# LAB2.net
KiCad netlist of a schematic drawn in Altium Designer
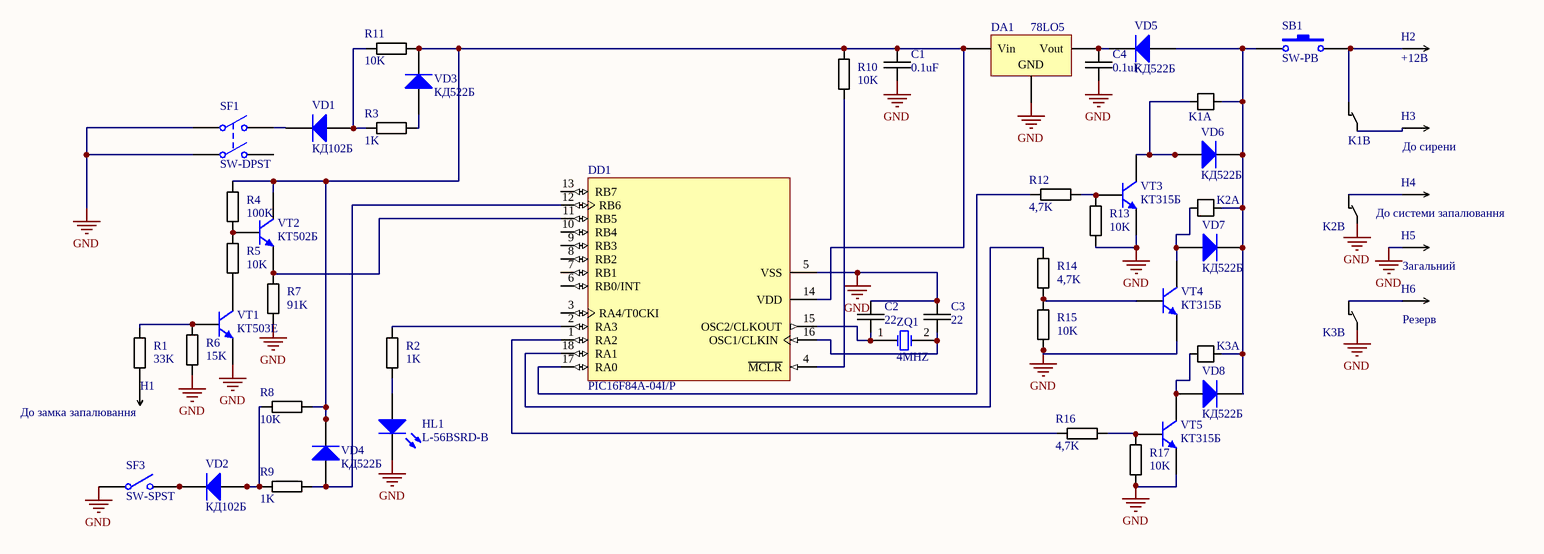
[diagram p0: LAB2.SchDoc]

(export (version "E")
  (design (tool "Eeschema 10.0.6"))
  (components
    (comp (ref "C1")
      (value "0.1uF")
      (footprint "CAPACITOR 1206")
      (libsource (lib "Maks_lib") (part "Capasitor"))
    )
    (comp (ref "C2")
      (value "22")
      (footprint "CAPACITOR 1206")
      (libsource (lib "Maks_lib") (part "Capasitor"))
    )
    (comp (ref "C3")
      (value "22")
      (footprint "CAPACITOR 1206")
      (libsource (lib "Maks_lib") (part "Capasitor"))
    )
    (comp (ref "C4")
      (value "0.1uF")
      (footprint "CAPACITOR 1206")
      (libsource (lib "Maks_lib") (part "Capasitor"))
    )
    (comp (ref "DA1")
      (value "78LO5")
      (footprint "D2PAK_N")
      (description "Voltage Regulator")
      (fields (field (name "PUBLISHER") "Altium Limited"))
      (libsource (lib "Miscellaneous Devices") (part "Volt Reg"))
    )
    (comp (ref "DD1")
      (value "PIC16F84A-04I/P")
      (footprint "PDIP300-P18")
      (libsource (lib "Altium Content Vault") (part "MC-8B-16F84A-IL18"))
    )
    (comp (ref "H1")
      (value "До замка запалювання")
      (footprint "Hole 2.5")
      (libsource (lib "Maks_lib") (part "Hole"))
    )
    (comp (ref "H2") (value "+12В") (footprint "Hole 2.5") (libsource (lib "Maks_lib") (part "Hole")))
    (comp (ref "H3") (value "До сирени") (footprint "Hole 2.5") (libsource (lib "Maks_lib") (part "Hole")))
    (comp (ref "H4")
      (value "До системи запалювання")
      (footprint "Hole 2.5")
      (libsource (lib "Maks_lib") (part "Hole"))
    )
    (comp (ref "H5") (value "Загальний") (footprint "Hole 2.5") (libsource (lib "Maks_lib") (part "Hole")))
    (comp (ref "H6") (value "Резерв") (footprint "Hole 2.5") (libsource (lib "Maks_lib") (part "Hole")))
    (comp (ref "HL1")
      (value "L-56BSRD-B")
      (footprint "LED-1")
      (description "Typical RED GaAs LED")
      (fields (field (name "PUBLISHER") "Altium Limited"))
      (libsource (lib "Miscellaneous Devices") (part "LED1"))
    )
    (comp (ref "K1")
      (value "Relay SPST")
      (footprint "g2rl-1a-e")
      (libsource (lib "Maks_lib") (part "Relay SPST"))
    )
    (comp (ref "K2")
      (value "Relay SPST")
      (footprint "g2rl-1a-e")
      (libsource (lib "Maks_lib") (part "Relay SPST"))
    )
    (comp (ref "K3")
      (value "Relay SPST")
      (footprint "g2rl-1a-e")
      (libsource (lib "Maks_lib") (part "Relay SPST"))
    )
    (comp (ref "R1") (value "33K") (footprint "Resistor 1206") (libsource (lib "Maks_lib") (part "Resistor")))
    (comp (ref "R2") (value "1K") (footprint "Resistor 1206") (libsource (lib "Maks_lib") (part "Resistor")))
    (comp (ref "R3") (value "1K") (footprint "Resistor 1206") (libsource (lib "Maks_lib") (part "Resistor")))
    (comp (ref "R4")
      (value "100K")
      (footprint "Resistor 1206")
      (libsource (lib "Maks_lib") (part "Resistor"))
    )
    (comp (ref "R5") (value "10K") (footprint "Resistor 1206") (libsource (lib "Maks_lib") (part "Resistor")))
    (comp (ref "R6") (value "15K") (footprint "Resistor 1206") (libsource (lib "Maks_lib") (part "Resistor")))
    (comp (ref "R7") (value "91K") (footprint "Resistor 1206") (libsource (lib "Maks_lib") (part "Resistor")))
    (comp (ref "R8") (value "10K") (footprint "Resistor 1206") (libsource (lib "Maks_lib") (part "Resistor")))
    (comp (ref "R9") (value "1K") (footprint "Resistor 1206") (libsource (lib "Maks_lib") (part "Resistor")))
    (comp (ref "R10")
      (value "10K")
      (footprint "Resistor 1206")
      (libsource (lib "Maks_lib") (part "Resistor"))
    )
    (comp (ref "R11")
      (value "10K")
      (footprint "Resistor 1206")
      (libsource (lib "Maks_lib") (part "Resistor"))
    )
    (comp (ref "R12")
      (value "4,7K")
      (footprint "Resistor 1206")
      (libsource (lib "Maks_lib") (part "Resistor"))
    )
    (comp (ref "R13")
      (value "10K")
      (footprint "Resistor 1206")
      (libsource (lib "Maks_lib") (part "Resistor"))
    )
    (comp (ref "R14")
      (value "4,7K")
      (footprint "Resistor 1206")
      (libsource (lib "Maks_lib") (part "Resistor"))
    )
    (comp (ref "R15")
      (value "10K")
      (footprint "Resistor 1206")
      (libsource (lib "Maks_lib") (part "Resistor"))
    )
    (comp (ref "R16")
      (value "4,7K")
      (footprint "Resistor 1206")
      (libsource (lib "Maks_lib") (part "Resistor"))
    )
    (comp (ref "R17")
      (value "10K")
      (footprint "Resistor 1206")
      (libsource (lib "Maks_lib") (part "Resistor"))
    )
    (comp (ref "SB1")
      (value "SW-PB")
      (footprint "SPST-2")
      (description "Switch")
      (fields (field (name "PUBLISHER") "Altium Limited"))
      (libsource (lib "Miscellaneous Devices") (part "SW-PB"))
    )
    (comp (ref "SF1")
      (value "SW-DPST")
      (footprint "DPST-4")
      (description "Double-Pole, Single-Throw Switch")
      (fields (field (name "PUBLISHER") "Altium Limited"))
      (libsource (lib "Miscellaneous Devices") (part "SW-DPST"))
    )
    (comp (ref "SF3")
      (value "SW-SPST")
      (footprint "SPST-2")
      (description "Single-Pole, Single-Throw Switch")
      (fields (field (name "PUBLISHER") "Altium Limited"))
      (libsource (lib "Miscellaneous Devices") (part "SW-SPST"))
    )
    (comp (ref "VD1")
      (value "КД102Б")
      (footprint "DO-35")
      (description "High Conductance Fast Diode")
      (fields (field (name "PUBLISHER") "Altium Limited"))
      (libsource (lib "Miscellaneous Devices") (part "Diode 1N4448"))
    )
    (comp (ref "VD2")
      (value "КД102Б")
      (footprint "DO-35")
      (description "High Conductance Fast Diode")
      (fields (field (name "PUBLISHER") "Altium Limited"))
      (libsource (lib "Miscellaneous Devices") (part "Diode 1N4448"))
    )
    (comp (ref "VD3")
      (value "КД522Б")
      (footprint "DO-35")
      (description "High Conductance Fast Diode")
      (fields (field (name "PUBLISHER") "Altium Limited"))
      (libsource (lib "Miscellaneous Devices") (part "Diode 1N4448"))
    )
    (comp (ref "VD4")
      (value "КД522Б")
      (footprint "DO-35")
      (description "High Conductance Fast Diode")
      (fields (field (name "PUBLISHER") "Altium Limited"))
      (libsource (lib "Miscellaneous Devices") (part "Diode 1N4448"))
    )
    (comp (ref "VD5")
      (value "КД522Б")
      (footprint "DO-35")
      (description "High Conductance Fast Diode")
      (fields (field (name "PUBLISHER") "Altium Limited"))
      (libsource (lib "Miscellaneous Devices") (part "Diode 1N4448"))
    )
    (comp (ref "VD6")
      (value "КД522Б")
      (footprint "DO-35")
      (description "High Conductance Fast Diode")
      (fields (field (name "PUBLISHER") "Altium Limited"))
      (libsource (lib "Miscellaneous Devices") (part "Diode 1N4448"))
    )
    (comp (ref "VD7")
      (value "КД522Б")
      (footprint "DO-35")
      (description "High Conductance Fast Diode")
      (fields (field (name "PUBLISHER") "Altium Limited"))
      (libsource (lib "Miscellaneous Devices") (part "Diode 1N4448"))
    )
    (comp (ref "VD8")
      (value "КД522Б")
      (footprint "DO-35")
      (description "High Conductance Fast Diode")
      (fields (field (name "PUBLISHER") "Altium Limited"))
      (libsource (lib "Miscellaneous Devices") (part "Diode 1N4448"))
    )
    (comp (ref "VT1")
      (value "КТ503Е")
      (footprint "TO-92A")
      (description "NPN General Purpose Amplifier")
      (fields (field (name "PUBLISHER") "Altium Limited"))
      (libsource (lib "FSC Discrete BJT") (part "2N3904"))
    )
    (comp (ref "VT2")
      (value "КТ502Б")
      (footprint "TO-92A")
      (description "NPN General Purpose Amplifier")
      (fields (field (name "PUBLISHER") "Altium Limited"))
      (libsource (lib "FSC Discrete BJT") (part "2N3904"))
    )
    (comp (ref "VT3")
      (value "КТ315Б")
      (footprint "TO-92A")
      (description "NPN General Purpose Amplifier")
      (fields (field (name "PUBLISHER") "Altium Limited"))
      (libsource (lib "FSC Discrete BJT") (part "2N3904"))
    )
    (comp (ref "VT4")
      (value "КТ315Б")
      (footprint "TO-92A")
      (description "NPN General Purpose Amplifier")
      (fields (field (name "PUBLISHER") "Altium Limited"))
      (libsource (lib "FSC Discrete BJT") (part "2N3904"))
    )
    (comp (ref "VT5")
      (value "КТ315Б")
      (footprint "TO-92A")
      (description "NPN General Purpose Amplifier")
      (fields (field (name "PUBLISHER") "Altium Limited"))
      (libsource (lib "FSC Discrete BJT") (part "2N3904"))
    )
    (comp (ref "ZQ1")
      (value "4MHZ")
      (footprint "R38")
      (description "Crystal Oscillator")
      (fields (field (name "PUBLISHER") "Altium Limited"))
      (libsource (lib "Miscellaneous Devices") (part "XTAL"))
    )
  )
  (nets
    (net (code "1") (name "GND") (class "Default")
      (node (ref "C1") (pin "2") (pinfunction "2_2") (pintype "passive"))
      (node (ref "C2") (pin "1") (pinfunction "1_1") (pintype "passive"))
      (node (ref "C3") (pin "1") (pinfunction "1_1") (pintype "passive"))
      (node (ref "C4") (pin "2") (pinfunction "2_2") (pintype "passive"))
      (node (ref "DA1") (pin "2") (pinfunction "GND_2") (pintype "passive"))
      (node (ref "DD1") (pin "5") (pinfunction "VSS_5") (pintype "power_in"))
      (node (ref "H5") (pin "0") (pinfunction "0_0") (pintype "passive"))
      (node (ref "HL1") (pin "2") (pinfunction "K_2") (pintype "passive"))
      (node (ref "K2") (pin "2") (pinfunction "2_2") (pintype "passive"))
      (node (ref "K3") (pin "2") (pinfunction "2_2") (pintype "passive"))
      (node (ref "R13") (pin "2") (pinfunction "2_2") (pintype "passive"))
      (node (ref "R15") (pin "2") (pinfunction "2_2") (pintype "passive"))
      (node (ref "R17") (pin "2") (pinfunction "2_2") (pintype "passive"))
      (node (ref "R6") (pin "2") (pinfunction "2_2") (pintype "passive"))
      (node (ref "R7") (pin "2") (pinfunction "2_2") (pintype "passive"))
      (node (ref "SF1") (pin "1") (pinfunction "COMMON1_1") (pintype "passive"))
      (node (ref "SF1") (pin "3") (pinfunction "COMMON2_3") (pintype "passive"))
      (node (ref "SF3") (pin "1") (pinfunction "COMMON_1") (pintype "passive"))
      (node (ref "VT1") (pin "1") (pinfunction "E_1") (pintype "passive"))
      (node (ref "VT3") (pin "1") (pinfunction "E_1") (pintype "passive"))
      (node (ref "VT4") (pin "1") (pinfunction "E_1") (pintype "passive"))
      (node (ref "VT5") (pin "1") (pinfunction "E_1") (pintype "passive"))
    )
    (net (code "2") (name "Net-(DA1-Vin)") (class "Default")
      (node (ref "C1") (pin "1") (pinfunction "1_1") (pintype "passive"))
      (node (ref "DA1") (pin "1") (pinfunction "Vin_1") (pintype "passive"))
      (node (ref "DD1") (pin "14") (pinfunction "VDD_14") (pintype "power_in"))
      (node (ref "R10") (pin "1") (pinfunction "1_1") (pintype "passive"))
      (node (ref "R11") (pin "2") (pinfunction "2_2") (pintype "passive"))
      (node (ref "R4") (pin "1") (pinfunction "1_1") (pintype "passive"))
      (node (ref "R8") (pin "1") (pinfunction "1_1") (pintype "passive"))
      (node (ref "VD3") (pin "2") (pinfunction "K_2") (pintype "passive"))
      (node (ref "VD4") (pin "2") (pinfunction "K_2") (pintype "passive"))
      (node (ref "VT2") (pin "3") (pinfunction "C_3") (pintype "passive"))
    )
    (net (code "3") (name "Net-(DA1-Vout)") (class "Default")
      (node (ref "C4") (pin "1") (pinfunction "1_1") (pintype "passive"))
      (node (ref "DA1") (pin "3") (pinfunction "Vout_3") (pintype "passive"))
      (node (ref "VD5") (pin "2") (pinfunction "K_2") (pintype "passive"))
    )
    (net (code "4") (name "Net-(DD1-OSC1{slash}CLKIN)") (class "Default")
      (node (ref "C3") (pin "2") (pinfunction "2_2") (pintype "passive"))
      (node (ref "DD1") (pin "16") (pinfunction "OSC1/CLKIN_16") (pintype "input"))
      (node (ref "ZQ1") (pin "2") (pinfunction "OSC2_2") (pintype "passive"))
    )
    (net (code "5") (name "Net-(DD1-OSC2{slash}CLKOUT)") (class "Default")
      (node (ref "C2") (pin "2") (pinfunction "2_2") (pintype "passive"))
      (node (ref "DD1") (pin "15") (pinfunction "OSC2/CLKOUT_15") (pintype "output"))
      (node (ref "ZQ1") (pin "1") (pinfunction "OSC1_1") (pintype "passive"))
    )
    (net (code "6") (name "Net-(DD1-RA0)") (class "Default")
      (node (ref "DD1") (pin "17") (pinfunction "RA0_17") (pintype "bidirectional"))
      (node (ref "R12") (pin "1") (pinfunction "1_1") (pintype "passive"))
    )
    (net (code "7") (name "Net-(DD1-RA1)") (class "Default")
      (node (ref "DD1") (pin "18") (pinfunction "RA1_18") (pintype "bidirectional"))
      (node (ref "R14") (pin "1") (pinfunction "1_1") (pintype "passive"))
    )
    (net (code "8") (name "Net-(DD1-RA2)") (class "Default")
      (node (ref "DD1") (pin "1") (pinfunction "RA2_1") (pintype "bidirectional"))
      (node (ref "R16") (pin "1") (pinfunction "1_1") (pintype "passive"))
    )
    (net (code "9") (name "Net-(DD1-RA3)") (class "Default")
      (node (ref "DD1") (pin "2") (pinfunction "RA3_2") (pintype "bidirectional"))
      (node (ref "R2") (pin "1") (pinfunction "1_1") (pintype "passive"))
    )
    (net (code "10") (name "Net-(DD1-RB5)") (class "Default")
      (node (ref "DD1") (pin "11") (pinfunction "RB5_11") (pintype "bidirectional"))
      (node (ref "R7") (pin "1") (pinfunction "1_1") (pintype "passive"))
      (node (ref "VT2") (pin "1") (pinfunction "E_1") (pintype "passive"))
    )
    (net (code "11") (name "Net-(DD1-RB6)") (class "Default")
      (node (ref "DD1") (pin "12") (pinfunction "RB6_12") (pintype "bidirectional"))
      (node (ref "R9") (pin "1") (pinfunction "1_1") (pintype "passive"))
      (node (ref "VD4") (pin "1") (pinfunction "A_1") (pintype "passive"))
    )
    (net (code "12") (name "Net-(DD1-~{MCLR})") (class "Default")
      (node (ref "DD1") (pin "4") (pinfunction "~{MCLR}_4") (pintype "input"))
      (node (ref "R10") (pin "2") (pinfunction "2_2") (pintype "passive"))
    )
    (net (code "13") (name "Net-(H1-Pad0)") (class "Default")
      (node (ref "H1") (pin "0") (pinfunction "0_0") (pintype "passive"))
      (node (ref "R1") (pin "2") (pinfunction "2_2") (pintype "passive"))
    )
    (net (code "14") (name "Net-(H2-Pad0)") (class "Default")
      (node (ref "H2") (pin "0") (pinfunction "0_0") (pintype "passive"))
      (node (ref "K1") (pin "3") (pinfunction "3_3") (pintype "passive"))
      (node (ref "SB1") (pin "2") (pinfunction "2_2") (pintype "passive"))
    )
    (net (code "15") (name "Net-(H3-Pad0)") (class "Default")
      (node (ref "H3") (pin "0") (pinfunction "0_0") (pintype "passive"))
      (node (ref "K1") (pin "2") (pinfunction "2_2") (pintype "passive"))
    )
    (net (code "16") (name "Net-(H4-Pad0)") (class "Default")
      (node (ref "H4") (pin "0") (pinfunction "0_0") (pintype "passive"))
      (node (ref "K2") (pin "3") (pinfunction "3_3") (pintype "passive"))
    )
    (net (code "17") (name "Net-(H6-Pad0)") (class "Default")
      (node (ref "H6") (pin "0") (pinfunction "0_0") (pintype "passive"))
      (node (ref "K3") (pin "3") (pinfunction "3_3") (pintype "passive"))
    )
    (net (code "18") (name "Net-(HL1-A)") (class "Default")
      (node (ref "HL1") (pin "1") (pinfunction "A_1") (pintype "passive"))
      (node (ref "R2") (pin "2") (pinfunction "2_2") (pintype "passive"))
    )
    (net (code "19") (name "Net-(SF1-NO1)") (class "Default")
      (node (ref "SF1") (pin "2") (pinfunction "NO1_2") (pintype "passive"))
      (node (ref "VD1") (pin "2") (pinfunction "K_2") (pintype "passive"))
    )
    (net (code "20") (name "Net-(SF3-NO)") (class "Default")
      (node (ref "SF3") (pin "2") (pinfunction "NO_2") (pintype "passive"))
      (node (ref "VD2") (pin "2") (pinfunction "K_2") (pintype "passive"))
    )
    (net (code "21") (name "Net-(VD1-A)") (class "Default")
      (node (ref "R11") (pin "1") (pinfunction "1_1") (pintype "passive"))
      (node (ref "R3") (pin "1") (pinfunction "1_1") (pintype "passive"))
      (node (ref "VD1") (pin "1") (pinfunction "A_1") (pintype "passive"))
    )
    (net (code "22") (name "Net-(VD2-A)") (class "Default")
      (node (ref "R8") (pin "2") (pinfunction "2_2") (pintype "passive"))
      (node (ref "R9") (pin "2") (pinfunction "2_2") (pintype "passive"))
      (node (ref "VD2") (pin "1") (pinfunction "A_1") (pintype "passive"))
    )
    (net (code "23") (name "Net-(VD3-A)") (class "Default")
      (node (ref "R3") (pin "2") (pinfunction "2_2") (pintype "passive"))
      (node (ref "VD3") (pin "1") (pinfunction "A_1") (pintype "passive"))
    )
    (net (code "24") (name "Net-(VD5-A)") (class "Default")
      (node (ref "K1") (pin "1") (pinfunction "1_1") (pintype "passive"))
      (node (ref "K2") (pin "1") (pinfunction "1_1") (pintype "passive"))
      (node (ref "K3") (pin "1") (pinfunction "1_1") (pintype "passive"))
      (node (ref "SB1") (pin "1") (pinfunction "1_1") (pintype "passive"))
      (node (ref "VD5") (pin "1") (pinfunction "A_1") (pintype "passive"))
      (node (ref "VD6") (pin "2") (pinfunction "K_2") (pintype "passive"))
      (node (ref "VD7") (pin "2") (pinfunction "K_2") (pintype "passive"))
      (node (ref "VD8") (pin "2") (pinfunction "K_2") (pintype "passive"))
    )
    (net (code "25") (name "Net-(VD6-A)") (class "Default")
      (node (ref "K1") (pin "0") (pinfunction "0_0") (pintype "passive"))
      (node (ref "VD6") (pin "1") (pinfunction "A_1") (pintype "passive"))
      (node (ref "VT3") (pin "3") (pinfunction "C_3") (pintype "passive"))
    )
    (net (code "26") (name "Net-(VD7-A)") (class "Default")
      (node (ref "K2") (pin "0") (pinfunction "0_0") (pintype "passive"))
      (node (ref "VD7") (pin "1") (pinfunction "A_1") (pintype "passive"))
      (node (ref "VT4") (pin "3") (pinfunction "C_3") (pintype "passive"))
    )
    (net (code "27") (name "Net-(VD8-A)") (class "Default")
      (node (ref "K3") (pin "0") (pinfunction "0_0") (pintype "passive"))
      (node (ref "VD8") (pin "1") (pinfunction "A_1") (pintype "passive"))
      (node (ref "VT5") (pin "3") (pinfunction "C_3") (pintype "passive"))
    )
    (net (code "28") (name "Net-(VT1-B)") (class "Default")
      (node (ref "R1") (pin "1") (pinfunction "1_1") (pintype "passive"))
      (node (ref "R6") (pin "1") (pinfunction "1_1") (pintype "passive"))
      (node (ref "VT1") (pin "2") (pinfunction "B_2") (pintype "passive"))
    )
    (net (code "29") (name "Net-(VT1-C)") (class "Default")
      (node (ref "R5") (pin "2") (pinfunction "2_2") (pintype "passive"))
      (node (ref "VT1") (pin "3") (pinfunction "C_3") (pintype "passive"))
    )
    (net (code "30") (name "Net-(VT2-B)") (class "Default")
      (node (ref "R4") (pin "2") (pinfunction "2_2") (pintype "passive"))
      (node (ref "R5") (pin "1") (pinfunction "1_1") (pintype "passive"))
      (node (ref "VT2") (pin "2") (pinfunction "B_2") (pintype "passive"))
    )
    (net (code "31") (name "Net-(VT3-B)") (class "Default")
      (node (ref "R12") (pin "2") (pinfunction "2_2") (pintype "passive"))
      (node (ref "R13") (pin "1") (pinfunction "1_1") (pintype "passive"))
      (node (ref "VT3") (pin "2") (pinfunction "B_2") (pintype "passive"))
    )
    (net (code "32") (name "Net-(VT4-B)") (class "Default")
      (node (ref "R14") (pin "2") (pinfunction "2_2") (pintype "passive"))
      (node (ref "R15") (pin "1") (pinfunction "1_1") (pintype "passive"))
      (node (ref "VT4") (pin "2") (pinfunction "B_2") (pintype "passive"))
    )
    (net (code "33") (name "Net-(VT5-B)") (class "Default")
      (node (ref "R16") (pin "2") (pinfunction "2_2") (pintype "passive"))
      (node (ref "R17") (pin "1") (pinfunction "1_1") (pintype "passive"))
      (node (ref "VT5") (pin "2") (pinfunction "B_2") (pintype "passive"))
    )
    (net (code "34") (name "unconnected-(DD1-RA4{slash}T0CKI-Pad3)") (class "Default")
      (node (ref "DD1") (pin "3") (pinfunction "RA4/T0CKI_3") (pintype "bidirectional"))
    )
    (net (code "35") (name "unconnected-(DD1-RB0{slash}INT-Pad6)") (class "Default")
      (node (ref "DD1") (pin "6") (pinfunction "RB0/INT_6") (pintype "bidirectional"))
    )
    (net (code "36") (name "unconnected-(DD1-RB1-Pad7)") (class "Default")
      (node (ref "DD1") (pin "7") (pinfunction "RB1_7") (pintype "bidirectional"))
    )
    (net (code "37") (name "unconnected-(DD1-RB2-Pad8)") (class "Default")
      (node (ref "DD1") (pin "8") (pinfunction "RB2_8") (pintype "bidirectional"))
    )
    (net (code "38") (name "unconnected-(DD1-RB3-Pad9)") (class "Default")
      (node (ref "DD1") (pin "9") (pinfunction "RB3_9") (pintype "bidirectional"))
    )
    (net (code "39") (name "unconnected-(DD1-RB4-Pad10)") (class "Default")
      (node (ref "DD1") (pin "10") (pinfunction "RB4_10") (pintype "bidirectional"))
    )
    (net (code "40") (name "unconnected-(DD1-RB7-Pad13)") (class "Default")
      (node (ref "DD1") (pin "13") (pinfunction "RB7_13") (pintype "bidirectional"))
    )
    (net (code "41") (name "unconnected-(SF1-NO2-Pad4)") (class "Default")
      (node (ref "SF1") (pin "4") (pinfunction "NO2_4") (pintype "passive"))
    )
  )
)
